# Sheet1.net
KiCad netlist of a schematic drawn in Altium Designer
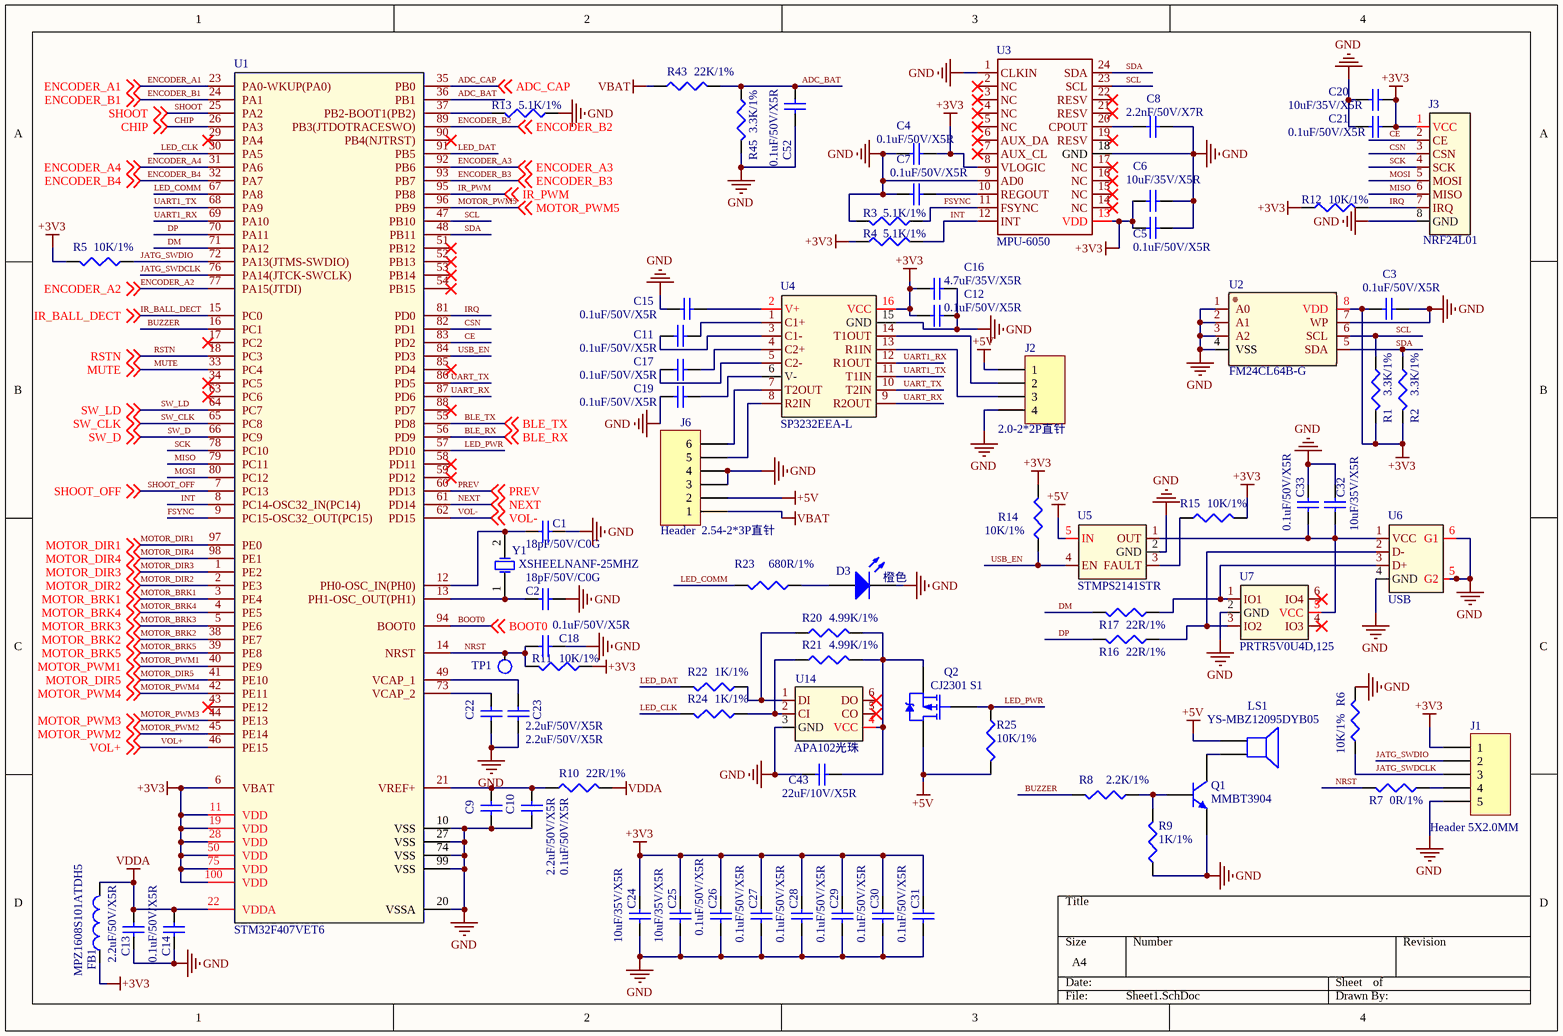
[diagram p0: Sheet1.SchDoc]

(export (version "E")
  (design (tool "Eeschema 10.0.6"))
  (components
    (comp (ref "C1")
      (value "18pF/50V/C0G")
      (footprint "C0603")
      (description "Capacitor (Semiconductor SIM Model)")
      (fields (field (name "PUBLISHER") "Altium Limited"))
      (libsource (lib "Miscellaneous Devices") (part "Cap Semi"))
    )
    (comp (ref "C2")
      (value "18pF/50V/C0G")
      (footprint "C0603")
      (description "Capacitor (Semiconductor SIM Model)")
      (fields (field (name "PUBLISHER") "Altium Limited"))
      (libsource (lib "Miscellaneous Devices") (part "Cap Semi"))
    )
    (comp (ref "C3")
      (value "0.1uF/50V/X5R")
      (footprint "C0603")
      (description "Capacitor (Semiconductor SIM Model)")
      (fields (field (name "PUBLISHER") "Altium Limited"))
      (libsource (lib "Miscellaneous Devices") (part "Cap Semi"))
    )
    (comp (ref "C4")
      (value "0.1uF/50V/X5R")
      (footprint "C0603")
      (description "Capacitor (Semiconductor SIM Model)")
      (fields (field (name "PUBLISHER") "Altium Limited"))
      (libsource (lib "Miscellaneous Devices") (part "Cap Semi"))
    )
    (comp (ref "C5")
      (value "0.1uF/50V/X5R")
      (footprint "C0603")
      (description "Capacitor (Semiconductor SIM Model)")
      (fields (field (name "PUBLISHER") "Altium Limited"))
      (libsource (lib "Miscellaneous Devices") (part "Cap Semi"))
    )
    (comp (ref "C6")
      (value "10uF/35V/X5R")
      (footprint "C0805")
      (description "Capacitor (Semiconductor SIM Model)")
      (fields (field (name "PUBLISHER") "Altium Limited"))
      (libsource (lib "Miscellaneous Devices") (part "Cap Semi"))
    )
    (comp (ref "C7")
      (value "0.1uF/50V/X5R")
      (footprint "C0603")
      (description "Capacitor (Semiconductor SIM Model)")
      (fields (field (name "PUBLISHER") "Altium Limited"))
      (libsource (lib "Miscellaneous Devices") (part "Cap Semi"))
    )
    (comp (ref "C8")
      (value "2.2nF/50V/X7R")
      (footprint "C0603")
      (description "Capacitor (Semiconductor SIM Model)")
      (fields (field (name "PUBLISHER") "Altium Limited"))
      (libsource (lib "Miscellaneous Devices") (part "Cap Semi"))
    )
    (comp (ref "C9")
      (value "2.2uF/50V/X5R")
      (footprint "C0603")
      (description "Capacitor (Semiconductor SIM Model)")
      (fields (field (name "PUBLISHER") "Altium Limited"))
      (libsource (lib "Miscellaneous Devices") (part "Cap Semi"))
    )
    (comp (ref "C10")
      (value "0.1uF/50V/X5R")
      (footprint "C0603")
      (description "Capacitor (Semiconductor SIM Model)")
      (fields (field (name "PUBLISHER") "Altium Limited"))
      (libsource (lib "Miscellaneous Devices") (part "Cap Semi"))
    )
    (comp (ref "C11")
      (value "0.1uF/50V/X5R")
      (footprint "C0603")
      (description "Capacitor (Semiconductor SIM Model)")
      (fields (field (name "PUBLISHER") "Altium Limited"))
      (libsource (lib "Miscellaneous Devices") (part "Cap Semi"))
    )
    (comp (ref "C12")
      (value "0.1uF/50V/X5R")
      (footprint "C0603")
      (description "Capacitor (Semiconductor SIM Model)")
      (fields (field (name "PUBLISHER") "Altium Limited"))
      (libsource (lib "Miscellaneous Devices") (part "Cap Semi"))
    )
    (comp (ref "C13")
      (value "2.2uF/50V/X5R")
      (footprint "C0603")
      (description "Capacitor (Semiconductor SIM Model)")
      (fields (field (name "PUBLISHER") "Altium Limited"))
      (libsource (lib "Miscellaneous Devices") (part "Cap Semi"))
    )
    (comp (ref "C14")
      (value "0.1uF/50V/X5R")
      (footprint "C0603")
      (description "Capacitor (Semiconductor SIM Model)")
      (fields (field (name "PUBLISHER") "Altium Limited"))
      (libsource (lib "Miscellaneous Devices") (part "Cap Semi"))
    )
    (comp (ref "C15")
      (value "0.1uF/50V/X5R")
      (footprint "C0603")
      (description "Capacitor (Semiconductor SIM Model)")
      (fields (field (name "PUBLISHER") "Altium Limited"))
      (libsource (lib "Miscellaneous Devices") (part "Cap Semi"))
    )
    (comp (ref "C16")
      (value "4.7uF/35V/X5R")
      (footprint "C0603")
      (description "Capacitor (Semiconductor SIM Model)")
      (fields (field (name "PUBLISHER") "Altium Limited"))
      (libsource (lib "Miscellaneous Devices") (part "Cap Semi"))
    )
    (comp (ref "C17")
      (value "0.1uF/50V/X5R")
      (footprint "C0603")
      (description "Capacitor (Semiconductor SIM Model)")
      (fields (field (name "PUBLISHER") "Altium Limited"))
      (libsource (lib "Miscellaneous Devices") (part "Cap Semi"))
    )
    (comp (ref "C18")
      (value "0.1uF/50V/X5R")
      (footprint "C0603")
      (description "Capacitor (Semiconductor SIM Model)")
      (fields (field (name "PUBLISHER") "Altium Limited"))
      (libsource (lib "Miscellaneous Devices") (part "Cap Semi"))
    )
    (comp (ref "C19")
      (value "0.1uF/50V/X5R")
      (footprint "C0603")
      (description "Capacitor (Semiconductor SIM Model)")
      (fields (field (name "PUBLISHER") "Altium Limited"))
      (libsource (lib "Miscellaneous Devices") (part "Cap Semi"))
    )
    (comp (ref "C20")
      (value "10uF/35V/X5R")
      (footprint "C0805")
      (description "Capacitor (Semiconductor SIM Model)")
      (fields (field (name "PUBLISHER") "Altium Limited"))
      (libsource (lib "Miscellaneous Devices") (part "Cap Semi"))
    )
    (comp (ref "C21")
      (value "0.1uF/50V/X5R")
      (footprint "C0603")
      (description "Capacitor (Semiconductor SIM Model)")
      (fields (field (name "PUBLISHER") "Altium Limited"))
      (libsource (lib "Miscellaneous Devices") (part "Cap Semi"))
    )
    (comp (ref "C22")
      (value "2.2uF/50V/X5R")
      (footprint "C0603")
      (description "Capacitor (Semiconductor SIM Model)")
      (fields (field (name "PUBLISHER") "Altium Limited"))
      (libsource (lib "Miscellaneous Devices") (part "Cap Semi"))
    )
    (comp (ref "C23")
      (value "2.2uF/50V/X5R")
      (footprint "C0603")
      (description "Capacitor (Semiconductor SIM Model)")
      (fields (field (name "PUBLISHER") "Altium Limited"))
      (libsource (lib "Miscellaneous Devices") (part "Cap Semi"))
    )
    (comp (ref "C24")
      (value "10uF/35V/X5R")
      (footprint "C0805")
      (description "Capacitor (Semiconductor SIM Model)")
      (fields (field (name "PUBLISHER") "Altium Limited"))
      (libsource (lib "Miscellaneous Devices") (part "Cap Semi"))
    )
    (comp (ref "C25")
      (value "10uF/35V/X5R")
      (footprint "C0805")
      (description "Capacitor (Semiconductor SIM Model)")
      (fields (field (name "PUBLISHER") "Altium Limited"))
      (libsource (lib "Miscellaneous Devices") (part "Cap Semi"))
    )
    (comp (ref "C26")
      (value "0.1uF/50V/X5R")
      (footprint "C0603")
      (description "Capacitor (Semiconductor SIM Model)")
      (fields (field (name "PUBLISHER") "Altium Limited"))
      (libsource (lib "Miscellaneous Devices") (part "Cap Semi"))
    )
    (comp (ref "C27")
      (value "0.1uF/50V/X5R")
      (footprint "C0603")
      (description "Capacitor (Semiconductor SIM Model)")
      (fields (field (name "PUBLISHER") "Altium Limited"))
      (libsource (lib "Miscellaneous Devices") (part "Cap Semi"))
    )
    (comp (ref "C28")
      (value "0.1uF/50V/X5R")
      (footprint "C0603")
      (description "Capacitor (Semiconductor SIM Model)")
      (fields (field (name "PUBLISHER") "Altium Limited"))
      (libsource (lib "Miscellaneous Devices") (part "Cap Semi"))
    )
    (comp (ref "C29")
      (value "0.1uF/50V/X5R")
      (footprint "C0603")
      (description "Capacitor (Semiconductor SIM Model)")
      (fields (field (name "PUBLISHER") "Altium Limited"))
      (libsource (lib "Miscellaneous Devices") (part "Cap Semi"))
    )
    (comp (ref "C30")
      (value "0.1uF/50V/X5R")
      (footprint "C0603")
      (description "Capacitor (Semiconductor SIM Model)")
      (fields (field (name "PUBLISHER") "Altium Limited"))
      (libsource (lib "Miscellaneous Devices") (part "Cap Semi"))
    )
    (comp (ref "C31")
      (value "0.1uF/50V/X5R")
      (footprint "C0603")
      (description "Capacitor (Semiconductor SIM Model)")
      (fields (field (name "PUBLISHER") "Altium Limited"))
      (libsource (lib "Miscellaneous Devices") (part "Cap Semi"))
    )
    (comp (ref "C32")
      (value "10uF/35V/X5R")
      (footprint "C0805")
      (description "Capacitor (Semiconductor SIM Model)")
      (fields (field (name "PUBLISHER") "Altium Limited"))
      (libsource (lib "Miscellaneous Devices") (part "Cap Semi"))
    )
    (comp (ref "C33")
      (value "0.1uF/50V/X5R")
      (footprint "C0603")
      (description "Capacitor (Semiconductor SIM Model)")
      (fields (field (name "PUBLISHER") "Altium Limited"))
      (libsource (lib "Miscellaneous Devices") (part "Cap Semi"))
    )
    (comp (ref "C43")
      (value "22uF/10V/X5R")
      (footprint "C0805")
      (description "Capacitor (Semiconductor SIM Model)")
      (fields (field (name "PUBLISHER") "Altium Limited"))
      (libsource (lib "Miscellaneous Devices") (part "Cap Semi"))
    )
    (comp (ref "C52")
      (value "0.1uF/50V/X5R")
      (footprint "C0603")
      (description "Capacitor (Semiconductor SIM Model)")
      (fields (field (name "PUBLISHER") "Altium Limited"))
      (libsource (lib "Miscellaneous Devices") (part "Cap Semi"))
    )
    (comp (ref "D3")
      (value "橙色")
      (footprint "LED0603")
      (description "Typical RED, GREEN, YELLOW, AMBER GaAs LED")
      (fields (field (name "PUBLISHER") "Altium Limited"))
      (libsource (lib "Miscellaneous Devices") (part "LED2"))
    )
    (comp (ref "FB1")
      (value "MPZ1608S101ATDH5")
      (footprint "R0603")
      (description "Inductor")
      (fields (field (name "PUBLISHER") "Altium Limited"))
      (libsource (lib "Miscellaneous Devices") (part "Inductor"))
    )
    (comp (ref "J1")
      (value "Header 5X2.0MM")
      (footprint "DIP-1X5_2.0MM")
      (description "Header, 5-Pin")
      (fields (field (name "PUBLISHER") "Altium Limited"))
      (libsource (lib "Miscellaneous Connectors") (part "Header 5"))
    )
    (comp (ref "J2")
      (value "2.0-2*2P直针")
      (footprint "DIP_2X2_2MM")
      (description "Header, 4-Pin")
      (fields (field (name "PUBLISHER") "Altium Limited"))
      (libsource (lib "Miscellaneous Connectors") (part "Header 4"))
    )
    (comp (ref "J3") (value "NRF24L01") (footprint "WIFI") (libsource (lib "Schlib1") (part "NRF24L01")))
    (comp (ref "J6")
      (value "Header  2.54-2*3P直针")
      (footprint "DIP_2X3_2.54")
      (description "Header, 6-Pin")
      (fields (field (name "PUBLISHER") "Altium Limited"))
      (libsource (lib "Miscellaneous Connectors") (part "Header 6"))
    )
    (comp (ref "LS1")
      (value "YS-MBZ12095DYB05")
      (footprint "DIP-P7.6")
      (description "Loudspeaker")
      (fields (field (name "PUBLISHER") "Altium Limited"))
      (libsource (lib "Miscellaneous Devices") (part "Speaker"))
    )
    (comp (ref "Q1") (value "MMBT3904") (footprint "SOT-23") (libsource (lib "Schlib1") (part "MMBT3904")))
    (comp (ref "Q2")
      (value "CJ2301 S1")
      (footprint "SOT-23")
      (description "P-Channel Power MOSFET")
      (fields (field (name "PUBLISHER") "Altium Limited"))
      (libsource (lib "Miscellaneous Devices") (part "PMOS-2"))
    )
    (comp (ref "R1")
      (value "3.3K/1%")
      (footprint "R0603")
      (description "Resistor")
      (fields (field (name "PUBLISHER") "Altium Limited"))
      (libsource (lib "Miscellaneous Devices") (part "Res3"))
    )
    (comp (ref "R2")
      (value "3.3K/1%")
      (footprint "R0603")
      (description "Resistor")
      (fields (field (name "PUBLISHER") "Altium Limited"))
      (libsource (lib "Miscellaneous Devices") (part "Res3"))
    )
    (comp (ref "R3")
      (value "5.1K/1%")
      (footprint "R0603")
      (description "Resistor")
      (fields (field (name "PUBLISHER") "Altium Limited"))
      (libsource (lib "Miscellaneous Devices") (part "Res3"))
    )
    (comp (ref "R4")
      (value "5.1K/1%")
      (footprint "R0603")
      (description "Resistor")
      (fields (field (name "PUBLISHER") "Altium Limited"))
      (libsource (lib "Miscellaneous Devices") (part "Res3"))
    )
    (comp (ref "R5")
      (value "10K/1%")
      (footprint "R0603")
      (description "Resistor")
      (fields (field (name "PUBLISHER") "Altium Limited"))
      (libsource (lib "Miscellaneous Devices") (part "Res3"))
    )
    (comp (ref "R6")
      (value "10K/1%")
      (footprint "R0603")
      (description "Resistor")
      (fields (field (name "PUBLISHER") "Altium Limited"))
      (libsource (lib "Miscellaneous Devices") (part "Res3"))
    )
    (comp (ref "R7")
      (value "0R/1%")
      (footprint "R0603")
      (description "Resistor")
      (fields (field (name "PUBLISHER") "Altium Limited"))
      (libsource (lib "Miscellaneous Devices") (part "Res3"))
    )
    (comp (ref "R8")
      (value "2.2K/1%")
      (footprint "R0603")
      (description "Resistor")
      (fields (field (name "PUBLISHER") "Altium Limited"))
      (libsource (lib "Miscellaneous Devices") (part "Res3"))
    )
    (comp (ref "R9")
      (value "1K/1%")
      (footprint "R0603")
      (description "Resistor")
      (fields (field (name "PUBLISHER") "Altium Limited"))
      (libsource (lib "Miscellaneous Devices") (part "Res3"))
    )
    (comp (ref "R10")
      (value "22R/1%")
      (footprint "R0603")
      (description "Resistor")
      (fields (field (name "PUBLISHER") "Altium Limited"))
      (libsource (lib "Miscellaneous Devices") (part "Res3"))
    )
    (comp (ref "R11")
      (value "10K/1%")
      (footprint "R0603")
      (description "Resistor")
      (fields (field (name "PUBLISHER") "Altium Limited"))
      (libsource (lib "Miscellaneous Devices") (part "Res3"))
    )
    (comp (ref "R12")
      (value "10K/1%")
      (footprint "R0603")
      (description "Resistor")
      (fields (field (name "PUBLISHER") "Altium Limited"))
      (libsource (lib "Miscellaneous Devices") (part "Res3"))
    )
    (comp (ref "R13")
      (value "5.1K/1%")
      (footprint "R0603")
      (description "Resistor")
      (fields (field (name "PUBLISHER") "Altium Limited"))
      (libsource (lib "Miscellaneous Devices") (part "Res3"))
    )
    (comp (ref "R14")
      (value "10K/1%")
      (footprint "R0603")
      (description "Resistor")
      (fields (field (name "PUBLISHER") "Altium Limited"))
      (libsource (lib "Miscellaneous Devices") (part "Res3"))
    )
    (comp (ref "R15")
      (value "10K/1%")
      (footprint "R0603")
      (description "Resistor")
      (fields (field (name "PUBLISHER") "Altium Limited"))
      (libsource (lib "Miscellaneous Devices") (part "Res3"))
    )
    (comp (ref "R16")
      (value "22R/1%")
      (footprint "R0603")
      (description "Resistor")
      (fields (field (name "PUBLISHER") "Altium Limited"))
      (libsource (lib "Miscellaneous Devices") (part "Res3"))
    )
    (comp (ref "R17")
      (value "22R/1%")
      (footprint "R0603")
      (description "Resistor")
      (fields (field (name "PUBLISHER") "Altium Limited"))
      (libsource (lib "Miscellaneous Devices") (part "Res3"))
    )
    (comp (ref "R20")
      (value "4.99K/1%")
      (footprint "R0603")
      (description "Resistor")
      (fields (field (name "PUBLISHER") "Altium Limited"))
      (libsource (lib "Miscellaneous Devices") (part "Res3"))
    )
    (comp (ref "R21")
      (value "4.99K/1%")
      (footprint "R0603")
      (description "Resistor")
      (fields (field (name "PUBLISHER") "Altium Limited"))
      (libsource (lib "Miscellaneous Devices") (part "Res3"))
    )
    (comp (ref "R22")
      (value "1K/1%")
      (footprint "R0603")
      (description "Resistor")
      (fields (field (name "PUBLISHER") "Altium Limited"))
      (libsource (lib "Miscellaneous Devices") (part "Res3"))
    )
    (comp (ref "R23")
      (value "680R/1%")
      (footprint "R0603")
      (description "Resistor")
      (fields (field (name "PUBLISHER") "Altium Limited"))
      (libsource (lib "Miscellaneous Devices") (part "Res3"))
    )
    (comp (ref "R24")
      (value "1K/1%")
      (footprint "R0603")
      (description "Resistor")
      (fields (field (name "PUBLISHER") "Altium Limited"))
      (libsource (lib "Miscellaneous Devices") (part "Res3"))
    )
    (comp (ref "R25")
      (value "10K/1%")
      (footprint "R0603")
      (description "Resistor")
      (fields (field (name "PUBLISHER") "Altium Limited"))
      (libsource (lib "Miscellaneous Devices") (part "Res3"))
    )
    (comp (ref "R43")
      (value "22K/1%")
      (footprint "R0603")
      (description "Resistor")
      (fields (field (name "PUBLISHER") "Altium Limited"))
      (libsource (lib "Miscellaneous Devices") (part "Res3"))
    )
    (comp (ref "R45")
      (value "3.3K/1%")
      (footprint "R0603")
      (description "Resistor")
      (fields (field (name "PUBLISHER") "Altium Limited"))
      (libsource (lib "Miscellaneous Devices") (part "Res3"))
    )
    (comp (ref "TP1") (value "TP") (footprint "TP") (libsource (lib "Schlib1") (part "TP")))
    (comp (ref "U1")
      (value "STM32F407VET6")
      (footprint "LQFP-100-14X")
      (libsource (lib "Schlib1") (part "STM32F407VET6"))
    )
    (comp (ref "U2")
      (value "FM24CL64B-G")
      (footprint "SOIC-8")
      (libsource (lib "Schlib1") (part "FM24CL64B-G"))
    )
    (comp (ref "U3") (value "MPU-6050") (footprint "QFN-24") (libsource (lib "Schlib1") (part "MPU-6050")))
    (comp (ref "U4")
      (value "SP3232EEA-L")
      (footprint "SSOP-16")
      (libsource (lib "Schlib1") (part "SP3232EEA-L"))
    )
    (comp (ref "U5")
      (value "STMPS2141STR")
      (footprint "SOT-23-5")
      (libsource (lib "Schlib1") (part "STMPS2141STR"))
    )
    (comp (ref "U6") (value "USB") (footprint "USB2.0") (libsource (lib "Schlib1") (part "USB")))
    (comp (ref "U7")
      (value "PRTR5V0U4D,125")
      (footprint "SOT-23-6")
      (libsource (lib "Schlib1") (part "PRTR5V0U4D,125"))
    )
    (comp (ref "U14") (value "APA102光珠") (footprint "LED-5X5") (libsource (lib "Schlib1") (part "APA102")))
    (comp (ref "Y1")
      (value "XSHEELNANF-25MHZ")
      (footprint "SMD_5032")
      (description "Crystal Oscillator")
      (fields (field (name "PUBLISHER") "Altium Limited"))
      (libsource (lib "Miscellaneous Devices") (part "XTAL"))
    )
  )
  (nets
    (net (code "1") (name "+3V3") (class "Default")
      (node (ref "C12") (pin "2") (pinfunction "2_2") (pintype "passive"))
      (node (ref "C16") (pin "2") (pinfunction "2_2") (pintype "passive"))
      (node (ref "C20") (pin "1") (pinfunction "1_1") (pintype "passive"))
      (node (ref "C21") (pin "1") (pinfunction "1_1") (pintype "passive"))
      (node (ref "C24") (pin "2") (pinfunction "2_2") (pintype "passive"))
      (node (ref "C25") (pin "1") (pinfunction "1_1") (pintype "passive"))
      (node (ref "C26") (pin "1") (pinfunction "1_1") (pintype "passive"))
      (node (ref "C27") (pin "2") (pinfunction "2_2") (pintype "passive"))
      (node (ref "C28") (pin "2") (pinfunction "2_2") (pintype "passive"))
      (node (ref "C29") (pin "2") (pinfunction "2_2") (pintype "passive"))
      (node (ref "C3") (pin "1") (pinfunction "1_1") (pintype "passive"))
      (node (ref "C30") (pin "1") (pinfunction "1_1") (pintype "passive"))
      (node (ref "C31") (pin "1") (pinfunction "1_1") (pintype "passive"))
      (node (ref "C4") (pin "1") (pinfunction "1_1") (pintype "passive"))
      (node (ref "C5") (pin "1") (pinfunction "1_1") (pintype "passive"))
      (node (ref "C6") (pin "1") (pinfunction "1_1") (pintype "passive"))
      (node (ref "FB1") (pin "2") (pinfunction "2_2") (pintype "passive"))
      (node (ref "J1") (pin "1") (pinfunction "1_1") (pintype "passive"))
      (node (ref "J3") (pin "1") (pinfunction "VCC_1") (pintype "passive"))
      (node (ref "R1") (pin "2") (pinfunction "2_2") (pintype "passive"))
      (node (ref "R11") (pin "1") (pinfunction "1_1") (pintype "passive"))
      (node (ref "R12") (pin "1") (pinfunction "1_1") (pintype "passive"))
      (node (ref "R14") (pin "2") (pinfunction "2_2") (pintype "passive"))
      (node (ref "R15") (pin "2") (pinfunction "2_2") (pintype "passive"))
      (node (ref "R2") (pin "2") (pinfunction "2_2") (pintype "passive"))
      (node (ref "R4") (pin "1") (pinfunction "1_1") (pintype "passive"))
      (node (ref "R5") (pin "2") (pinfunction "2_2") (pintype "passive"))
      (node (ref "U1") (pin "100") (pinfunction "VDD_100") (pintype "passive"))
      (node (ref "U1") (pin "11") (pinfunction "VDD_11") (pintype "passive"))
      (node (ref "U1") (pin "19") (pinfunction "VDD_19") (pintype "passive"))
      (node (ref "U1") (pin "28") (pinfunction "VDD_28") (pintype "passive"))
      (node (ref "U1") (pin "50") (pinfunction "VDD_50") (pintype "passive"))
      (node (ref "U1") (pin "6") (pinfunction "VBAT_6") (pintype "passive"))
      (node (ref "U1") (pin "75") (pinfunction "VDD_75") (pintype "passive"))
      (node (ref "U2") (pin "8") (pinfunction "VDD_8") (pintype "passive"))
      (node (ref "U3") (pin "13") (pinfunction "VDD_13") (pintype "passive"))
      (node (ref "U3") (pin "8") (pinfunction "VLOGIC_8") (pintype "passive"))
      (node (ref "U4") (pin "16") (pinfunction "VCC_16") (pintype "passive"))
    )
    (net (code "2") (name "+5V") (class "Default")
      (node (ref "J2") (pin "1") (pinfunction "1_1") (pintype "passive"))
      (node (ref "J6") (pin "2") (pinfunction "2_2") (pintype "passive"))
      (node (ref "LS1") (pin "1") (pinfunction "1_1") (pintype "passive"))
      (node (ref "Q2") (pin "2") (pinfunction "D_2") (pintype "passive"))
      (node (ref "R25") (pin "2") (pinfunction "2_2") (pintype "passive"))
      (node (ref "U5") (pin "5") (pinfunction "IN_5") (pintype "passive"))
    )
    (net (code "3") (name "/ADC_BAT") (class "Default")
      (node (ref "C52") (pin "1") (pinfunction "1_1") (pintype "passive"))
      (node (ref "R43") (pin "2") (pinfunction "2_2") (pintype "passive"))
      (node (ref "R45") (pin "1") (pinfunction "1_1") (pintype "passive"))
      (node (ref "U1") (pin "36") (pinfunction "PB1_36") (pintype "passive"))
    )
    (net (code "4") (name "/BUZZER") (class "Default")
      (node (ref "R8") (pin "2") (pinfunction "2_2") (pintype "passive"))
      (node (ref "U1") (pin "16") (pinfunction "PC1_16") (pintype "passive"))
    )
    (net (code "5") (name "/CE") (class "Default")
      (node (ref "J3") (pin "2") (pinfunction "CE_2") (pintype "passive"))
      (node (ref "U1") (pin "83") (pinfunction "PD2_83") (pintype "passive"))
    )
    (net (code "6") (name "/CSN") (class "Default")
      (node (ref "J3") (pin "3") (pinfunction "CSN_3") (pintype "passive"))
      (node (ref "U1") (pin "82") (pinfunction "PD1_82") (pintype "passive"))
    )
    (net (code "7") (name "/DM") (class "Default")
      (node (ref "R17") (pin "2") (pinfunction "2_2") (pintype "passive"))
      (node (ref "U1") (pin "71") (pinfunction "PA12_71") (pintype "passive"))
    )
    (net (code "8") (name "/DP") (class "Default")
      (node (ref "R16") (pin "2") (pinfunction "2_2") (pintype "passive"))
      (node (ref "U1") (pin "70") (pinfunction "PA11_70") (pintype "passive"))
    )
    (net (code "9") (name "/FSYNC") (class "Default")
      (node (ref "R3") (pin "1") (pinfunction "1_1") (pintype "passive"))
      (node (ref "U1") (pin "9") (pinfunction "PC15-OSC32_OUT(PC15)_9") (pintype "passive"))
      (node (ref "U3") (pin "11") (pinfunction "FSYNC_11") (pintype "passive"))
    )
    (net (code "10") (name "/INT") (class "Default")
      (node (ref "R4") (pin "2") (pinfunction "2_2") (pintype "passive"))
      (node (ref "U1") (pin "8") (pinfunction "PC14-OSC32_IN(PC14)_8") (pintype "passive"))
      (node (ref "U3") (pin "12") (pinfunction "INT_12") (pintype "passive"))
    )
    (net (code "11") (name "/IRQ") (class "Default")
      (node (ref "J3") (pin "7") (pinfunction "IRQ_7") (pintype "passive"))
      (node (ref "R12") (pin "2") (pinfunction "2_2") (pintype "passive"))
      (node (ref "U1") (pin "81") (pinfunction "PD0_81") (pintype "passive"))
    )
    (net (code "12") (name "/JATG_SWDCLK") (class "Default")
      (node (ref "J1") (pin "3") (pinfunction "3_3") (pintype "passive"))
      (node (ref "R6") (pin "1") (pinfunction "1_1") (pintype "passive"))
      (node (ref "U1") (pin "76") (pinfunction "PA14(JTCK-SWCLK)_76") (pintype "passive"))
    )
    (net (code "13") (name "/JATG_SWDIO") (class "Default")
      (node (ref "J1") (pin "2") (pinfunction "2_2") (pintype "passive"))
      (node (ref "R5") (pin "1") (pinfunction "1_1") (pintype "passive"))
      (node (ref "U1") (pin "72") (pinfunction "PA13(JTMS-SWDIO)_72") (pintype "passive"))
    )
    (net (code "14") (name "/LED_CLK") (class "Default")
      (node (ref "R24") (pin "2") (pinfunction "2_2") (pintype "passive"))
      (node (ref "U1") (pin "30") (pinfunction "PA5_30") (pintype "passive"))
    )
    (net (code "15") (name "/LED_COMM") (class "Default")
      (node (ref "R23") (pin "2") (pinfunction "2_2") (pintype "passive"))
      (node (ref "U1") (pin "67") (pinfunction "PA8_67") (pintype "passive"))
    )
    (net (code "16") (name "/LED_DAT") (class "Default")
      (node (ref "R22") (pin "2") (pinfunction "2_2") (pintype "passive"))
      (node (ref "U1") (pin "91") (pinfunction "PB5_91") (pintype "passive"))
    )
    (net (code "17") (name "/LED_PWR") (class "Default")
      (node (ref "Q2") (pin "1") (pinfunction "G_1") (pintype "passive"))
      (node (ref "R25") (pin "1") (pinfunction "1_1") (pintype "passive"))
      (node (ref "U1") (pin "57") (pinfunction "PD10_57") (pintype "passive"))
    )
    (net (code "18") (name "/MISO") (class "Default")
      (node (ref "J3") (pin "6") (pinfunction "MISO_6") (pintype "passive"))
      (node (ref "U1") (pin "79") (pinfunction "PC11_79") (pintype "passive"))
    )
    (net (code "19") (name "/MOSI") (class "Default")
      (node (ref "J3") (pin "5") (pinfunction "MOSI_5") (pintype "passive"))
      (node (ref "U1") (pin "80") (pinfunction "PC12_80") (pintype "passive"))
    )
    (net (code "20") (name "/NRST") (class "Default")
      (node (ref "C18") (pin "2") (pinfunction "2_2") (pintype "passive"))
      (node (ref "R11") (pin "2") (pinfunction "2_2") (pintype "passive"))
      (node (ref "R7") (pin "2") (pinfunction "2_2") (pintype "passive"))
      (node (ref "TP1") (pin "1") (pinfunction "1_1") (pintype "passive"))
      (node (ref "U1") (pin "14") (pinfunction "NRST_14") (pintype "passive"))
    )
    (net (code "21") (name "/SCK") (class "Default")
      (node (ref "J3") (pin "4") (pinfunction "SCK_4") (pintype "passive"))
      (node (ref "U1") (pin "78") (pinfunction "PC10_78") (pintype "passive"))
    )
    (net (code "22") (name "/SCL") (class "Default")
      (node (ref "R1") (pin "1") (pinfunction "1_1") (pintype "passive"))
      (node (ref "U1") (pin "47") (pinfunction "PB10_47") (pintype "passive"))
      (node (ref "U2") (pin "6") (pinfunction "SCL_6") (pintype "passive"))
      (node (ref "U3") (pin "23") (pinfunction "SCL_23") (pintype "passive"))
    )
    (net (code "23") (name "/SDA") (class "Default")
      (node (ref "R2") (pin "1") (pinfunction "1_1") (pintype "passive"))
      (node (ref "U1") (pin "48") (pinfunction "PB11_48") (pintype "passive"))
      (node (ref "U2") (pin "5") (pinfunction "SDA_5") (pintype "passive"))
      (node (ref "U3") (pin "24") (pinfunction "SDA_24") (pintype "passive"))
    )
    (net (code "24") (name "/UART1_RX") (class "Default")
      (node (ref "U1") (pin "69") (pinfunction "PA10_69") (pintype "passive"))
      (node (ref "U4") (pin "12") (pinfunction "R1OUT_12") (pintype "passive"))
    )
    (net (code "25") (name "/UART1_TX") (class "Default")
      (node (ref "U1") (pin "68") (pinfunction "PA9_68") (pintype "passive"))
      (node (ref "U4") (pin "11") (pinfunction "T1IN_11") (pintype "passive"))
    )
    (net (code "26") (name "/UART_RX") (class "Default")
      (node (ref "U1") (pin "87") (pinfunction "PD6_87") (pintype "passive"))
      (node (ref "U4") (pin "9") (pinfunction "R2OUT_9") (pintype "passive"))
    )
    (net (code "27") (name "/UART_TX") (class "Default")
      (node (ref "U1") (pin "86") (pinfunction "PD5_86") (pintype "passive"))
      (node (ref "U4") (pin "10") (pinfunction "T2IN_10") (pintype "passive"))
    )
    (net (code "28") (name "/USB_EN") (class "Default")
      (node (ref "R14") (pin "1") (pinfunction "1_1") (pintype "passive"))
      (node (ref "U1") (pin "84") (pinfunction "PD3_84") (pintype "passive"))
      (node (ref "U5") (pin "4") (pinfunction "EN_4") (pintype "passive"))
    )
    (net (code "29") (name "ADC_CAP") (class "Default")
      (node (ref "U1") (pin "35") (pinfunction "PB0_35") (pintype "passive"))
    )
    (net (code "30") (name "BLE_RX") (class "Default")
      (node (ref "U1") (pin "56") (pinfunction "PD9_56") (pintype "passive"))
    )
    (net (code "31") (name "BLE_TX") (class "Default")
      (node (ref "U1") (pin "55") (pinfunction "PD8_55") (pintype "passive"))
    )
    (net (code "32") (name "BOOT0") (class "Default")
      (node (ref "U1") (pin "94") (pinfunction "BOOT0_94") (pintype "passive"))
    )
    (net (code "33") (name "CHIP") (class "Default")
      (node (ref "U1") (pin "26") (pinfunction "PA3_26") (pintype "passive"))
    )
    (net (code "34") (name "ENCODER_A1") (class "Default")
      (node (ref "U1") (pin "23") (pinfunction "PA0-WKUP(PA0)_23") (pintype "passive"))
    )
    (net (code "35") (name "ENCODER_A2") (class "Default")
      (node (ref "U1") (pin "77") (pinfunction "PA15(JTDI)_77") (pintype "passive"))
    )
    (net (code "36") (name "ENCODER_A3") (class "Default")
      (node (ref "U1") (pin "92") (pinfunction "PB6_92") (pintype "passive"))
    )
    (net (code "37") (name "ENCODER_A4") (class "Default")
      (node (ref "U1") (pin "31") (pinfunction "PA6_31") (pintype "passive"))
    )
    (net (code "38") (name "ENCODER_B1") (class "Default")
      (node (ref "U1") (pin "24") (pinfunction "PA1_24") (pintype "passive"))
    )
    (net (code "39") (name "ENCODER_B2") (class "Default")
      (node (ref "U1") (pin "89") (pinfunction "PB3(JTDOTRACESWO)_89") (pintype "passive"))
    )
    (net (code "40") (name "ENCODER_B3") (class "Default")
      (node (ref "U1") (pin "93") (pinfunction "PB7_93") (pintype "passive"))
    )
    (net (code "41") (name "ENCODER_B4") (class "Default")
      (node (ref "U1") (pin "32") (pinfunction "PA7_32") (pintype "passive"))
    )
    (net (code "42") (name "GND") (class "Default")
      (node (ref "C1") (pin "2") (pinfunction "2_2") (pintype "passive"))
      (node (ref "C10") (pin "2") (pinfunction "2_2") (pintype "passive"))
      (node (ref "C12") (pin "1") (pinfunction "1_1") (pintype "passive"))
      (node (ref "C13") (pin "1") (pinfunction "1_1") (pintype "passive"))
      (node (ref "C14") (pin "1") (pinfunction "1_1") (pintype "passive"))
      (node (ref "C15") (pin "2") (pinfunction "2_2") (pintype "passive"))
      (node (ref "C16") (pin "1") (pinfunction "1_1") (pintype "passive"))
      (node (ref "C18") (pin "1") (pinfunction "1_1") (pintype "passive"))
      (node (ref "C19") (pin "2") (pinfunction "2_2") (pintype "passive"))
      (node (ref "C2") (pin "2") (pinfunction "2_2") (pintype "passive"))
      (node (ref "C20") (pin "2") (pinfunction "2_2") (pintype "passive"))
      (node (ref "C21") (pin "2") (pinfunction "2_2") (pintype "passive"))
      (node (ref "C22") (pin "2") (pinfunction "2_2") (pintype "passive"))
      (node (ref "C23") (pin "2") (pinfunction "2_2") (pintype "passive"))
      (node (ref "C24") (pin "1") (pinfunction "1_1") (pintype "passive"))
      (node (ref "C25") (pin "2") (pinfunction "2_2") (pintype "passive"))
      (node (ref "C26") (pin "2") (pinfunction "2_2") (pintype "passive"))
      (node (ref "C27") (pin "1") (pinfunction "1_1") (pintype "passive"))
      (node (ref "C28") (pin "1") (pinfunction "1_1") (pintype "passive"))
      (node (ref "C29") (pin "1") (pinfunction "1_1") (pintype "passive"))
      (node (ref "C3") (pin "2") (pinfunction "2_2") (pintype "passive"))
      (node (ref "C30") (pin "2") (pinfunction "2_2") (pintype "passive"))
      (node (ref "C31") (pin "2") (pinfunction "2_2") (pintype "passive"))
      (node (ref "C32") (pin "2") (pinfunction "2_2") (pintype "passive"))
      (node (ref "C33") (pin "2") (pinfunction "2_2") (pintype "passive"))
      (node (ref "C4") (pin "2") (pinfunction "2_2") (pintype "passive"))
      (node (ref "C43") (pin "1") (pinfunction "1_1") (pintype "passive"))
      (node (ref "C5") (pin "2") (pinfunction "2_2") (pintype "passive"))
      (node (ref "C52") (pin "2") (pinfunction "2_2") (pintype "passive"))
      (node (ref "C6") (pin "2") (pinfunction "2_2") (pintype "passive"))
      (node (ref "C7") (pin "2") (pinfunction "2_2") (pintype "passive"))
      (node (ref "C8") (pin "2") (pinfunction "2_2") (pintype "passive"))
      (node (ref "C9") (pin "2") (pinfunction "2_2") (pintype "passive"))
      (node (ref "D3") (pin "2") (pinfunction "K_2") (pintype "passive"))
      (node (ref "J1") (pin "5") (pinfunction "5_5") (pintype "passive"))
      (node (ref "J2") (pin "4") (pinfunction "4_4") (pintype "passive"))
      (node (ref "J3") (pin "8") (pinfunction "GND_8") (pintype "passive"))
      (node (ref "J6") (pin "3") (pinfunction "3_3") (pintype "passive"))
      (node (ref "J6") (pin "4") (pinfunction "4_4") (pintype "passive"))
      (node (ref "Q1") (pin "2") (pinfunction "E_2") (pintype "passive"))
      (node (ref "R13") (pin "1") (pinfunction "1_1") (pintype "passive"))
      (node (ref "R3") (pin "2") (pinfunction "2_2") (pintype "passive"))
      (node (ref "R45") (pin "2") (pinfunction "2_2") (pintype "passive"))
      (node (ref "R6") (pin "2") (pinfunction "2_2") (pintype "passive"))
      (node (ref "R9") (pin "1") (pinfunction "1_1") (pintype "passive"))
      (node (ref "U1") (pin "10") (pinfunction "VSS_10") (pintype "passive"))
      (node (ref "U1") (pin "20") (pinfunction "VSSA_20") (pintype "passive"))
      (node (ref "U1") (pin "27") (pinfunction "VSS_27") (pintype "passive"))
      (node (ref "U1") (pin "74") (pinfunction "VSS_74") (pintype "passive"))
      (node (ref "U1") (pin "99") (pinfunction "VSS_99") (pintype "passive"))
      (node (ref "U14") (pin "3") (pinfunction "GND_3") (pintype "passive"))
      (node (ref "U2") (pin "1") (pinfunction "A0_1") (pintype "passive"))
      (node (ref "U2") (pin "2") (pinfunction "A1_2") (pintype "passive"))
      (node (ref "U2") (pin "3") (pinfunction "A2_3") (pintype "passive"))
      (node (ref "U2") (pin "4") (pinfunction "VSS_4") (pintype "passive"))
      (node (ref "U2") (pin "7") (pinfunction "WP_7") (pintype "passive"))
      (node (ref "U3") (pin "1") (pinfunction "CLKIN_1") (pintype "passive"))
      (node (ref "U3") (pin "18") (pinfunction "GND_18") (pintype "passive"))
      (node (ref "U3") (pin "9") (pinfunction "AD0_9") (pintype "passive"))
      (node (ref "U4") (pin "15") (pinfunction "GND_15") (pintype "passive"))
      (node (ref "U5") (pin "2") (pinfunction "GND_2") (pintype "passive"))
      (node (ref "U6") (pin "4") (pinfunction "GND_4") (pintype "passive"))
      (node (ref "U6") (pin "5") (pinfunction "G2_5") (pintype "passive"))
      (node (ref "U6") (pin "6") (pinfunction "G1_6") (pintype "passive"))
      (node (ref "U7") (pin "2") (pinfunction "GND_2") (pintype "passive"))
    )
    (net (code "43") (name "IR_BALL_DECT") (class "Default")
      (node (ref "U1") (pin "15") (pinfunction "PC0_15") (pintype "passive"))
    )
    (net (code "44") (name "IR_PWM") (class "Default")
      (node (ref "U1") (pin "95") (pinfunction "PB8_95") (pintype "passive"))
    )
    (net (code "45") (name "MOTOR_BRK1") (class "Default")
      (node (ref "U1") (pin "3") (pinfunction "PE4_3") (pintype "passive"))
    )
    (net (code "46") (name "MOTOR_BRK2") (class "Default")
      (node (ref "U1") (pin "38") (pinfunction "PE7_38") (pintype "passive"))
    )
    (net (code "47") (name "MOTOR_BRK3") (class "Default")
      (node (ref "U1") (pin "5") (pinfunction "PE6_5") (pintype "passive"))
    )
    (net (code "48") (name "MOTOR_BRK4") (class "Default")
      (node (ref "U1") (pin "4") (pinfunction "PE5_4") (pintype "passive"))
    )
    (net (code "49") (name "MOTOR_BRK5") (class "Default")
      (node (ref "U1") (pin "39") (pinfunction "PE8_39") (pintype "passive"))
    )
    (net (code "50") (name "MOTOR_DIR1") (class "Default")
      (node (ref "U1") (pin "97") (pinfunction "PE0_97") (pintype "passive"))
    )
    (net (code "51") (name "MOTOR_DIR2") (class "Default")
      (node (ref "U1") (pin "2") (pinfunction "PE3_2") (pintype "passive"))
    )
    (net (code "52") (name "MOTOR_DIR3") (class "Default")
      (node (ref "U1") (pin "1") (pinfunction "PE2_1") (pintype "passive"))
    )
    (net (code "53") (name "MOTOR_DIR4") (class "Default")
      (node (ref "U1") (pin "98") (pinfunction "PE1_98") (pintype "passive"))
    )
    (net (code "54") (name "MOTOR_DIR5") (class "Default")
      (node (ref "U1") (pin "41") (pinfunction "PE10_41") (pintype "passive"))
    )
    (net (code "55") (name "MOTOR_PWM1") (class "Default")
      (node (ref "U1") (pin "40") (pinfunction "PE9_40") (pintype "passive"))
    )
    (net (code "56") (name "MOTOR_PWM2") (class "Default")
      (node (ref "U1") (pin "45") (pinfunction "PE14_45") (pintype "passive"))
    )
    (net (code "57") (name "MOTOR_PWM3") (class "Default")
      (node (ref "U1") (pin "44") (pinfunction "PE13_44") (pintype "passive"))
    )
    (net (code "58") (name "MOTOR_PWM4") (class "Default")
      (node (ref "U1") (pin "42") (pinfunction "PE11_42") (pintype "passive"))
    )
    (net (code "59") (name "MOTOR_PWM5") (class "Default")
      (node (ref "U1") (pin "96") (pinfunction "PB9_96") (pintype "passive"))
    )
    (net (code "60") (name "MUTE") (class "Default")
      (node (ref "U1") (pin "33") (pinfunction "PC4_33") (pintype "passive"))
    )
    (net (code "61") (name "NEXT") (class "Default")
      (node (ref "U1") (pin "61") (pinfunction "PD14_61") (pintype "passive"))
    )
    (net (code "62") (name "Net-(D3-A)") (class "Default")
      (node (ref "D3") (pin "1") (pinfunction "A_1") (pintype "passive"))
      (node (ref "R23") (pin "1") (pinfunction "1_1") (pintype "passive"))
    )
    (net (code "63") (name "Net-(J1-Pad4)") (class "Default")
      (node (ref "J1") (pin "4") (pinfunction "4_4") (pintype "passive"))
      (node (ref "R7") (pin "1") (pinfunction "1_1") (pintype "passive"))
    )
    (net (code "64") (name "Net-(Q1-B)") (class "Default")
      (node (ref "Q1") (pin "1") (pinfunction "B_1") (pintype "passive"))
      (node (ref "R8") (pin "1") (pinfunction "1_1") (pintype "passive"))
      (node (ref "R9") (pin "2") (pinfunction "2_2") (pintype "passive"))
    )
    (net (code "65") (name "Net-(Q1-C)") (class "Default")
      (node (ref "LS1") (pin "2") (pinfunction "2_2") (pintype "passive"))
      (node (ref "Q1") (pin "3") (pinfunction "C_3") (pintype "passive"))
    )
    (net (code "66") (name "Net-(Q2-S)") (class "Default")
      (node (ref "C43") (pin "2") (pinfunction "2_2") (pintype "passive"))
      (node (ref "Q2") (pin "3") (pinfunction "S_3") (pintype "passive"))
      (node (ref "R20") (pin "2") (pinfunction "2_2") (pintype "passive"))
      (node (ref "R21") (pin "2") (pinfunction "2_2") (pintype "passive"))
      (node (ref "U14") (pin "4") (pinfunction "VCC_4") (pintype "passive"))
    )
    (net (code "67") (name "Net-(U1-PB2-BOOT1(PB2))") (class "Default")
      (node (ref "R13") (pin "2") (pinfunction "2_2") (pintype "passive"))
      (node (ref "U1") (pin "37") (pinfunction "PB2-BOOT1(PB2)_37") (pintype "passive"))
    )
    (net (code "68") (name "Net-(U1-PH0-OSC_IN(PH0))") (class "Default")
      (node (ref "C1") (pin "1") (pinfunction "1_1") (pintype "passive"))
      (node (ref "U1") (pin "12") (pinfunction "PH0-OSC_IN(PH0)_12") (pintype "passive"))
      (node (ref "Y1") (pin "2") (pinfunction "OSC2_2") (pintype "passive"))
    )
    (net (code "69") (name "Net-(U1-PH1-OSC_OUT(PH1))") (class "Default")
      (node (ref "C2") (pin "1") (pinfunction "1_1") (pintype "passive"))
      (node (ref "U1") (pin "13") (pinfunction "PH1-OSC_OUT(PH1)_13") (pintype "passive"))
      (node (ref "Y1") (pin "1") (pinfunction "OSC1_1") (pintype "passive"))
    )
    (net (code "70") (name "Net-(U1-VCAP_1)") (class "Default")
      (node (ref "C23") (pin "1") (pinfunction "1_1") (pintype "passive"))
      (node (ref "U1") (pin "49") (pinfunction "VCAP_1_49") (pintype "passive"))
    )
    (net (code "71") (name "Net-(U1-VCAP_2)") (class "Default")
      (node (ref "C22") (pin "1") (pinfunction "1_1") (pintype "passive"))
      (node (ref "U1") (pin "73") (pinfunction "VCAP_2_73") (pintype "passive"))
    )
    (net (code "72") (name "Net-(U1-VREF+)") (class "Default")
      (node (ref "C10") (pin "1") (pinfunction "1_1") (pintype "passive"))
      (node (ref "C9") (pin "1") (pinfunction "1_1") (pintype "passive"))
      (node (ref "R10") (pin "1") (pinfunction "1_1") (pintype "passive"))
      (node (ref "U1") (pin "21") (pinfunction "VREF+_21") (pintype "passive"))
    )
    (net (code "73") (name "Net-(U3-CPOUT)") (class "Default")
      (node (ref "C8") (pin "1") (pinfunction "1_1") (pintype "passive"))
      (node (ref "U3") (pin "20") (pinfunction "CPOUT_20") (pintype "passive"))
    )
    (net (code "74") (name "Net-(U3-REGOUT)") (class "Default")
      (node (ref "C7") (pin "1") (pinfunction "1_1") (pintype "passive"))
      (node (ref "U3") (pin "10") (pinfunction "REGOUT_10") (pintype "passive"))
    )
    (net (code "75") (name "Net-(U4-C1+)") (class "Default")
      (node (ref "C11") (pin "1") (pinfunction "1_1") (pintype "passive"))
      (node (ref "U4") (pin "1") (pinfunction "C1+_1") (pintype "passive"))
    )
    (net (code "76") (name "Net-(U4-C1-)") (class "Default")
      (node (ref "C11") (pin "2") (pinfunction "2_2") (pintype "passive"))
      (node (ref "U4") (pin "3") (pinfunction "C1-_3") (pintype "passive"))
    )
    (net (code "77") (name "Net-(U4-C2+)") (class "Default")
      (node (ref "C17") (pin "1") (pinfunction "1_1") (pintype "passive"))
      (node (ref "U4") (pin "4") (pinfunction "C2+_4") (pintype "passive"))
    )
    (net (code "78") (name "Net-(U4-C2-)") (class "Default")
      (node (ref "C17") (pin "2") (pinfunction "2_2") (pintype "passive"))
      (node (ref "U4") (pin "5") (pinfunction "C2-_5") (pintype "passive"))
    )
    (net (code "79") (name "Net-(U4-R1IN)") (class "Default")
      (node (ref "J2") (pin "3") (pinfunction "3_3") (pintype "passive"))
      (node (ref "U4") (pin "13") (pinfunction "R1IN_13") (pintype "passive"))
    )
    (net (code "80") (name "Net-(U4-R2IN)") (class "Default")
      (node (ref "J6") (pin "5") (pinfunction "5_5") (pintype "passive"))
      (node (ref "U4") (pin "8") (pinfunction "R2IN_8") (pintype "passive"))
    )
    (net (code "81") (name "Net-(U4-T1OUT)") (class "Default")
      (node (ref "J2") (pin "2") (pinfunction "2_2") (pintype "passive"))
      (node (ref "U4") (pin "14") (pinfunction "T1OUT_14") (pintype "passive"))
    )
    (net (code "82") (name "Net-(U4-T2OUT)") (class "Default")
      (node (ref "J6") (pin "6") (pinfunction "6_6") (pintype "passive"))
      (node (ref "U4") (pin "7") (pinfunction "T2OUT_7") (pintype "passive"))
    )
    (net (code "83") (name "Net-(U4-V+)") (class "Default")
      (node (ref "C15") (pin "1") (pinfunction "1_1") (pintype "passive"))
      (node (ref "U4") (pin "2") (pinfunction "V+_2") (pintype "passive"))
    )
    (net (code "84") (name "Net-(U4-V-)") (class "Default")
      (node (ref "C19") (pin "1") (pinfunction "1_1") (pintype "passive"))
      (node (ref "U4") (pin "6") (pinfunction "V-_6") (pintype "passive"))
    )
    (net (code "85") (name "Net-(U5-FAULT)") (class "Default")
      (node (ref "R15") (pin "1") (pinfunction "1_1") (pintype "passive"))
      (node (ref "U5") (pin "3") (pinfunction "FAULT_3") (pintype "passive"))
    )
    (net (code "86") (name "Net-(U5-OUT)") (class "Default")
      (node (ref "C32") (pin "1") (pinfunction "1_1") (pintype "passive"))
      (node (ref "C33") (pin "1") (pinfunction "1_1") (pintype "passive"))
      (node (ref "U5") (pin "1") (pinfunction "OUT_1") (pintype "passive"))
      (node (ref "U6") (pin "1") (pinfunction "VCC_1") (pintype "passive"))
      (node (ref "U7") (pin "5") (pinfunction "VCC_5") (pintype "passive"))
    )
    (net (code "87") (name "Net-(U6-D+)") (class "Default")
      (node (ref "R17") (pin "1") (pinfunction "1_1") (pintype "passive"))
      (node (ref "U6") (pin "3") (pinfunction "D+_3") (pintype "passive"))
      (node (ref "U7") (pin "1") (pinfunction "IO1_1") (pintype "passive"))
    )
    (net (code "88") (name "Net-(U6-D-)") (class "Default")
      (node (ref "R16") (pin "1") (pinfunction "1_1") (pintype "passive"))
      (node (ref "U6") (pin "2") (pinfunction "D-_2") (pintype "passive"))
      (node (ref "U7") (pin "3") (pinfunction "IO2_3") (pintype "passive"))
    )
    (net (code "89") (name "Net-(U14-CI)") (class "Default")
      (node (ref "R21") (pin "1") (pinfunction "1_1") (pintype "passive"))
      (node (ref "R24") (pin "1") (pinfunction "1_1") (pintype "passive"))
      (node (ref "U14") (pin "2") (pinfunction "CI_2") (pintype "passive"))
    )
    (net (code "90") (name "Net-(U14-DI)") (class "Default")
      (node (ref "R20") (pin "1") (pinfunction "1_1") (pintype "passive"))
      (node (ref "R22") (pin "1") (pinfunction "1_1") (pintype "passive"))
      (node (ref "U14") (pin "1") (pinfunction "DI_1") (pintype "passive"))
    )
    (net (code "91") (name "PREV") (class "Default")
      (node (ref "U1") (pin "60") (pinfunction "PD13_60") (pintype "passive"))
    )
    (net (code "92") (name "RSTN") (class "Default")
      (node (ref "U1") (pin "18") (pinfunction "PC3_18") (pintype "passive"))
    )
    (net (code "93") (name "SHOOT") (class "Default")
      (node (ref "U1") (pin "25") (pinfunction "PA2_25") (pintype "passive"))
    )
    (net (code "94") (name "SHOOT_OFF") (class "Default")
      (node (ref "U1") (pin "7") (pinfunction "PC13_7") (pintype "passive"))
    )
    (net (code "95") (name "SW_CLK") (class "Default")
      (node (ref "U1") (pin "65") (pinfunction "PC8_65") (pintype "passive"))
    )
    (net (code "96") (name "SW_D") (class "Default")
      (node (ref "U1") (pin "66") (pinfunction "PC9_66") (pintype "passive"))
    )
    (net (code "97") (name "SW_LD") (class "Default")
      (node (ref "U1") (pin "64") (pinfunction "PC7_64") (pintype "passive"))
    )
    (net (code "98") (name "VBAT") (class "Default")
      (node (ref "J6") (pin "1") (pinfunction "1_1") (pintype "passive"))
      (node (ref "R43") (pin "1") (pinfunction "1_1") (pintype "passive"))
    )
    (net (code "99") (name "VDDA") (class "Default")
      (node (ref "C13") (pin "2") (pinfunction "2_2") (pintype "passive"))
      (node (ref "C14") (pin "2") (pinfunction "2_2") (pintype "passive"))
      (node (ref "FB1") (pin "1") (pinfunction "1_1") (pintype "passive"))
      (node (ref "R10") (pin "2") (pinfunction "2_2") (pintype "passive"))
      (node (ref "U1") (pin "22") (pinfunction "VDDA_22") (pintype "passive"))
    )
    (net (code "100") (name "VOL+") (class "Default")
      (node (ref "U1") (pin "46") (pinfunction "PE15_46") (pintype "passive"))
    )
    (net (code "101") (name "VOL-") (class "Default")
      (node (ref "U1") (pin "62") (pinfunction "PD15_62") (pintype "passive"))
    )
    (net (code "102") (name "unconnected-(U1-PA4-Pad29)") (class "Default")
      (node (ref "U1") (pin "29") (pinfunction "PA4_29") (pintype "passive+no_connect"))
    )
    (net (code "103") (name "unconnected-(U1-PB4(NJTRST)-Pad90)") (class "Default")
      (node (ref "U1") (pin "90") (pinfunction "PB4(NJTRST)_90") (pintype "passive+no_connect"))
    )
    (net (code "104") (name "unconnected-(U1-PB12-Pad51)") (class "Default")
      (node (ref "U1") (pin "51") (pinfunction "PB12_51") (pintype "passive+no_connect"))
    )
    (net (code "105") (name "unconnected-(U1-PB13-Pad52)") (class "Default")
      (node (ref "U1") (pin "52") (pinfunction "PB13_52") (pintype "passive+no_connect"))
    )
    (net (code "106") (name "unconnected-(U1-PB14-Pad53)") (class "Default")
      (node (ref "U1") (pin "53") (pinfunction "PB14_53") (pintype "passive+no_connect"))
    )
    (net (code "107") (name "unconnected-(U1-PB15-Pad54)") (class "Default")
      (node (ref "U1") (pin "54") (pinfunction "PB15_54") (pintype "passive+no_connect"))
    )
    (net (code "108") (name "unconnected-(U1-PC2-Pad17)") (class "Default")
      (node (ref "U1") (pin "17") (pinfunction "PC2_17") (pintype "passive+no_connect"))
    )
    (net (code "109") (name "unconnected-(U1-PC5-Pad34)") (class "Default")
      (node (ref "U1") (pin "34") (pinfunction "PC5_34") (pintype "passive+no_connect"))
    )
    (net (code "110") (name "unconnected-(U1-PC6-Pad63)") (class "Default")
      (node (ref "U1") (pin "63") (pinfunction "PC6_63") (pintype "passive+no_connect"))
    )
    (net (code "111") (name "unconnected-(U1-PD4-Pad85)") (class "Default")
      (node (ref "U1") (pin "85") (pinfunction "PD4_85") (pintype "passive+no_connect"))
    )
    (net (code "112") (name "unconnected-(U1-PD7-Pad88)") (class "Default")
      (node (ref "U1") (pin "88") (pinfunction "PD7_88") (pintype "passive+no_connect"))
    )
    (net (code "113") (name "unconnected-(U1-PD11-Pad58)") (class "Default")
      (node (ref "U1") (pin "58") (pinfunction "PD11_58") (pintype "passive+no_connect"))
    )
    (net (code "114") (name "unconnected-(U1-PD12-Pad59)") (class "Default")
      (node (ref "U1") (pin "59") (pinfunction "PD12_59") (pintype "passive+no_connect"))
    )
    (net (code "115") (name "unconnected-(U1-PE12-Pad43)") (class "Default")
      (node (ref "U1") (pin "43") (pinfunction "PE12_43") (pintype "passive+no_connect"))
    )
    (net (code "116") (name "unconnected-(U3-AUX_CL-Pad7)") (class "Default")
      (node (ref "U3") (pin "7") (pinfunction "AUX_CL_7") (pintype "passive+no_connect"))
    )
    (net (code "117") (name "unconnected-(U3-AUX_DA-Pad6)") (class "Default")
      (node (ref "U3") (pin "6") (pinfunction "AUX_DA_6") (pintype "passive+no_connect"))
    )
    (net (code "118") (name "unconnected-(U3-NC-Pad2)") (class "Default")
      (node (ref "U3") (pin "2") (pinfunction "NC_2") (pintype "passive+no_connect"))
    )
    (net (code "119") (name "unconnected-(U3-NC-Pad3)") (class "Default")
      (node (ref "U3") (pin "3") (pinfunction "NC_3") (pintype "passive+no_connect"))
    )
    (net (code "120") (name "unconnected-(U3-NC-Pad4)") (class "Default")
      (node (ref "U3") (pin "4") (pinfunction "NC_4") (pintype "passive+no_connect"))
    )
    (net (code "121") (name "unconnected-(U3-NC-Pad5)") (class "Default")
      (node (ref "U3") (pin "5") (pinfunction "NC_5") (pintype "passive+no_connect"))
    )
    (net (code "122") (name "unconnected-(U3-NC-Pad14)") (class "Default")
      (node (ref "U3") (pin "14") (pinfunction "NC_14") (pintype "passive+no_connect"))
    )
    (net (code "123") (name "unconnected-(U3-NC-Pad15)") (class "Default")
      (node (ref "U3") (pin "15") (pinfunction "NC_15") (pintype "passive+no_connect"))
    )
    (net (code "124") (name "unconnected-(U3-NC-Pad16)") (class "Default")
      (node (ref "U3") (pin "16") (pinfunction "NC_16") (pintype "passive+no_connect"))
    )
    (net (code "125") (name "unconnected-(U3-NC-Pad17)") (class "Default")
      (node (ref "U3") (pin "17") (pinfunction "NC_17") (pintype "passive+no_connect"))
    )
    (net (code "126") (name "unconnected-(U3-RESV-Pad19)") (class "Default")
      (node (ref "U3") (pin "19") (pinfunction "RESV_19") (pintype "passive+no_connect"))
    )
    (net (code "127") (name "unconnected-(U3-RESV-Pad21)") (class "Default")
      (node (ref "U3") (pin "21") (pinfunction "RESV_21") (pintype "passive+no_connect"))
    )
    (net (code "128") (name "unconnected-(U3-RESV-Pad22)") (class "Default")
      (node (ref "U3") (pin "22") (pinfunction "RESV_22") (pintype "passive+no_connect"))
    )
    (net (code "129") (name "unconnected-(U7-IO3-Pad4)") (class "Default")
      (node (ref "U7") (pin "4") (pinfunction "IO3_4") (pintype "passive+no_connect"))
    )
    (net (code "130") (name "unconnected-(U7-IO4-Pad6)") (class "Default")
      (node (ref "U7") (pin "6") (pinfunction "IO4_6") (pintype "passive+no_connect"))
    )
    (net (code "131") (name "unconnected-(U14-CO-Pad5)") (class "Default")
      (node (ref "U14") (pin "5") (pinfunction "CO_5") (pintype "passive+no_connect"))
    )
    (net (code "132") (name "unconnected-(U14-DO-Pad6)") (class "Default")
      (node (ref "U14") (pin "6") (pinfunction "DO_6") (pintype "passive+no_connect"))
    )
  )
)
